# RTI-Dome-wire.net
KiCad netlist of a schematic drawn in EAGLE
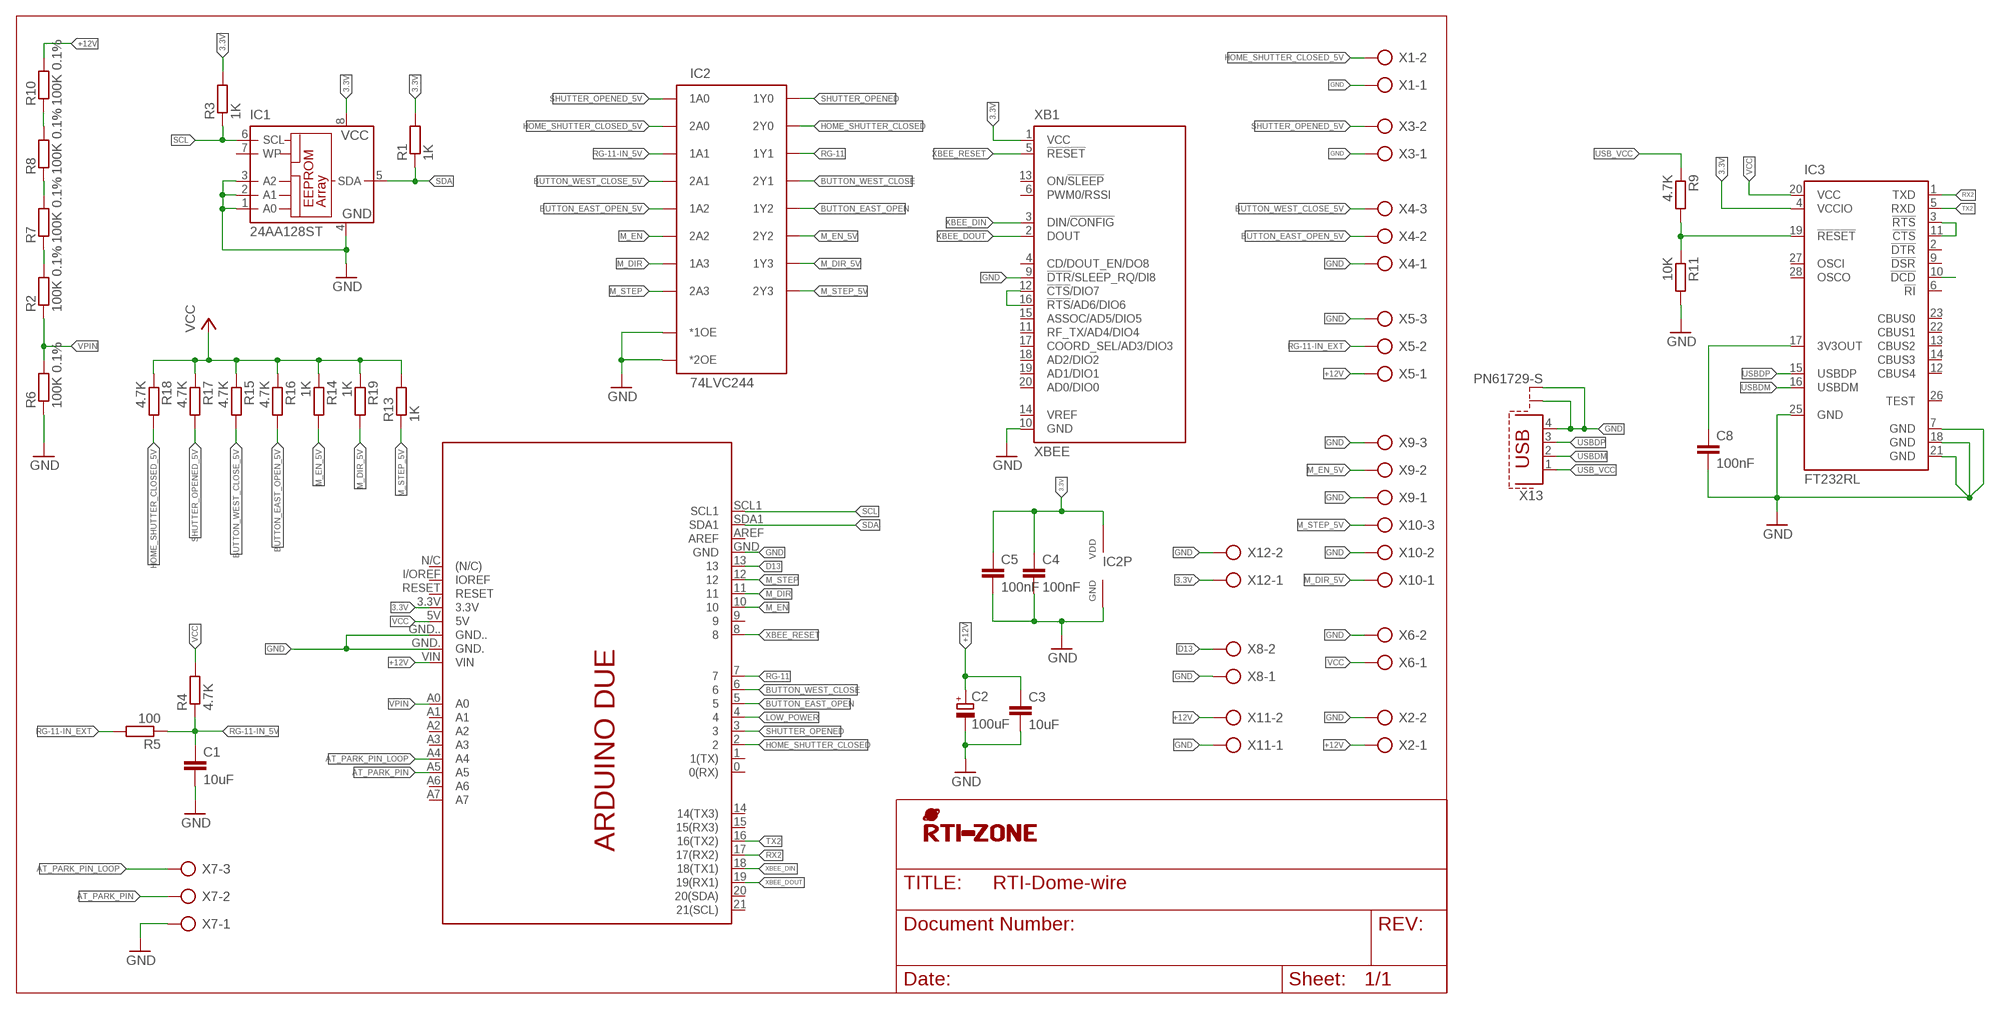
[diagram p0: schematic, sheet 1]

(export (version "E")
  (design (tool "Eeschema 10.0.6"))
  (components
    (comp (ref "C1")
      (value "10uF")
      (footprint "eagle-import:C0805")
      (libsource (lib "eagle-import") (part "C-EU'0805'"))
    )
    (comp (ref "C2")
      (value "100uF")
      (footprint "eagle-import:UD-10X10_NICHICON")
      (libsource (lib "eagle-import") (part "CPOL-EU"))
    )
    (comp (ref "C3")
      (value "10uF")
      (footprint "eagle-import:C0805")
      (libsource (lib "eagle-import") (part "C-EU'0805'"))
    )
    (comp (ref "C4")
      (value "100nF")
      (footprint "eagle-import:C0805")
      (libsource (lib "eagle-import") (part "C-EU'0805'"))
    )
    (comp (ref "C5")
      (value "100nF")
      (footprint "eagle-import:C0805")
      (libsource (lib "eagle-import") (part "C-EU'0805'"))
    )
    (comp (ref "C8")
      (value "100nF")
      (footprint "eagle-import:C0805")
      (libsource (lib "eagle-import") (part "C-EU'0805'"))
    )
    (comp (ref "IC1")
      (value "24AA128ST")
      (footprint "eagle-import:TSSOP8")
      (fields (field (name "MF") "MICROCHIP") (field (name "MPN") "24AA128-I/ST"))
      (libsource (lib "eagle-import") (part "24STAA128"))
    )
    (comp (ref "IC2")
      (value "74LVC244")
      (footprint "eagle-import:TSSOP20")
      (libsource (lib "eagle-import") (part "74244LVC"))
    )
    (comp (ref "IC3")
      (value "FT232RL")
      (footprint "eagle-import:SSOP28")
      (libsource (lib "eagle-import") (part "FT232RL"))
    )
    (comp (ref "PCB1")
      (value "ARDUINO_DUE_SHIELD_SHORT")
      (footprint "eagle-import:ARDUINO_DUE_SHIELD_SHORT")
      (libsource (lib "eagle-import") (part "ARDUINO_DUE_SHIELD_SHORT"))
    )
    (comp (ref "R1")
      (value "1K")
      (footprint "eagle-import:R0805")
      (libsource (lib "eagle-import") (part "R-EU'0805'"))
    )
    (comp (ref "R2")
      (value "100K 0.1%")
      (footprint "eagle-import:R0805")
      (libsource (lib "eagle-import") (part "R-EU'0805'"))
    )
    (comp (ref "R3")
      (value "1K")
      (footprint "eagle-import:R0805")
      (libsource (lib "eagle-import") (part "R-EU'0805'"))
    )
    (comp (ref "R4")
      (value "4.7K")
      (footprint "eagle-import:R0805")
      (libsource (lib "eagle-import") (part "R-EU'0805'"))
    )
    (comp (ref "R5")
      (value "100")
      (footprint "eagle-import:R0805")
      (libsource (lib "eagle-import") (part "R-EU'0805'"))
    )
    (comp (ref "R6")
      (value "100K 0.1%")
      (footprint "eagle-import:R0805")
      (libsource (lib "eagle-import") (part "R-EU'0805'"))
    )
    (comp (ref "R7")
      (value "100K 0.1%")
      (footprint "eagle-import:R0805")
      (libsource (lib "eagle-import") (part "R-EU'0805'"))
    )
    (comp (ref "R8")
      (value "100K 0.1%")
      (footprint "eagle-import:R0805")
      (libsource (lib "eagle-import") (part "R-EU'0805'"))
    )
    (comp (ref "R9")
      (value "4.7K")
      (footprint "eagle-import:R0805")
      (libsource (lib "eagle-import") (part "R-EU'0805'"))
    )
    (comp (ref "R10")
      (value "100K 0.1%")
      (footprint "eagle-import:R0805")
      (libsource (lib "eagle-import") (part "R-EU'0805'"))
    )
    (comp (ref "R11")
      (value "10K")
      (footprint "eagle-import:R0805")
      (libsource (lib "eagle-import") (part "R-EU'0805'"))
    )
    (comp (ref "R13")
      (value "1K")
      (footprint "eagle-import:R0805")
      (libsource (lib "eagle-import") (part "R-EU'0805'"))
    )
    (comp (ref "R14")
      (value "1K")
      (footprint "eagle-import:R0805")
      (libsource (lib "eagle-import") (part "R-EU'0805'"))
    )
    (comp (ref "R15")
      (value "4.7K")
      (footprint "eagle-import:R0805")
      (libsource (lib "eagle-import") (part "R-EU'0805'"))
    )
    (comp (ref "R16")
      (value "4.7K")
      (footprint "eagle-import:R0805")
      (libsource (lib "eagle-import") (part "R-EU'0805'"))
    )
    (comp (ref "R17")
      (value "4.7K")
      (footprint "eagle-import:R0805")
      (libsource (lib "eagle-import") (part "R-EU'0805'"))
    )
    (comp (ref "R18")
      (value "4.7K")
      (footprint "eagle-import:R0805")
      (libsource (lib "eagle-import") (part "R-EU'0805'"))
    )
    (comp (ref "R19")
      (value "1K")
      (footprint "eagle-import:R0805")
      (libsource (lib "eagle-import") (part "R-EU'0805'"))
    )
    (comp (ref "U$4")
      (value "RTI-LOGO_BIG")
      (footprint "eagle-import:LOGO_BIG")
      (libsource (lib "eagle-import") (part "RTI-LOGO_BIG"))
    )
    (comp (ref "X1")
      (value "AK500/2")
      (footprint "eagle-import:AK500_2")
      (libsource (lib "eagle-import") (part "AK500/2"))
    )
    (comp (ref "X2")
      (value "AK500/2")
      (footprint "eagle-import:AK500_2")
      (libsource (lib "eagle-import") (part "AK500/2"))
    )
    (comp (ref "X3")
      (value "AK500/2")
      (footprint "eagle-import:AK500_2")
      (libsource (lib "eagle-import") (part "AK500/2"))
    )
    (comp (ref "X4")
      (value "AK500/3")
      (footprint "eagle-import:AK500_3")
      (libsource (lib "eagle-import") (part "AK500/3"))
    )
    (comp (ref "X5")
      (value "AK500/3")
      (footprint "eagle-import:AK500_3")
      (libsource (lib "eagle-import") (part "AK500/3"))
    )
    (comp (ref "X6")
      (value "AK500/2")
      (footprint "eagle-import:AK500_2")
      (libsource (lib "eagle-import") (part "AK500/2"))
    )
    (comp (ref "X7")
      (value "AK500/3")
      (footprint "eagle-import:AK500_3")
      (libsource (lib "eagle-import") (part "AK500/3"))
    )
    (comp (ref "X8")
      (value "AK500/2")
      (footprint "eagle-import:AK500_2")
      (libsource (lib "eagle-import") (part "AK500/2"))
    )
    (comp (ref "X9")
      (value "AK500/3")
      (footprint "eagle-import:AK500_3")
      (libsource (lib "eagle-import") (part "AK500/3"))
    )
    (comp (ref "X10")
      (value "AK500/3")
      (footprint "eagle-import:AK500_3")
      (libsource (lib "eagle-import") (part "AK500/3"))
    )
    (comp (ref "X11")
      (value "AK500/2")
      (footprint "eagle-import:AK500_2")
      (libsource (lib "eagle-import") (part "AK500/2"))
    )
    (comp (ref "X12")
      (value "AK500/2")
      (footprint "eagle-import:AK500_2")
      (libsource (lib "eagle-import") (part "AK500/2"))
    )
    (comp (ref "X13")
      (value "PN61729-S")
      (footprint "eagle-import:PN61729-S")
      (libsource (lib "eagle-import") (part "PN61729-S"))
    )
    (comp (ref "XB1")
      (value "XBEE")
      (footprint "eagle-import:XBEE")
      (fields (field (name "MPN") "XBP24-Z7UIT-004"))
      (libsource (lib "eagle-import") (part "XBEE"))
    )
  )
  (nets
    (net (code "1") (name "+12V") (class "Default")
      (node (ref "C2") (pin "+") (pinfunction "+_+") (pintype "passive"))
      (node (ref "C3") (pin "1") (pinfunction "1_1") (pintype "passive"))
      (node (ref "PCB1") (pin "VIN") (pinfunction "VIN_VIN") (pintype "bidirectional"))
      (node (ref "R10") (pin "2") (pinfunction "2_2") (pintype "passive"))
      (node (ref "X11") (pin "2") (pinfunction "KL_2") (pintype "passive"))
      (node (ref "X2") (pin "1") (pinfunction "KL_1") (pintype "passive"))
      (node (ref "X5") (pin "1") (pinfunction "KL_1") (pintype "passive"))
    )
    (net (code "2") (name "3.3V") (class "Default")
      (node (ref "C4") (pin "1") (pinfunction "1_1") (pintype "passive"))
      (node (ref "C5") (pin "1") (pinfunction "1_1") (pintype "passive"))
      (node (ref "IC1") (pin "8") (pinfunction "VCC_8") (pintype "power_in"))
      (node (ref "IC2") (pin "P$20") (pinfunction "VDD_P$20") (pintype "power_in"))
      (node (ref "IC3") (pin "4") (pinfunction "VCCIO_4") (pintype "power_in"))
      (node (ref "PCB1") (pin "3.3V") (pinfunction "3.3V_3.3V") (pintype "bidirectional"))
      (node (ref "R1") (pin "2") (pinfunction "2_2") (pintype "passive"))
      (node (ref "R3") (pin "2") (pinfunction "2_2") (pintype "passive"))
      (node (ref "X12") (pin "1") (pinfunction "KL_1") (pintype "passive"))
      (node (ref "XB1") (pin "1") (pinfunction "VCC_1") (pintype "power_in"))
    )
    (net (code "3") (name "AT_PARK_PIN") (class "Default")
      (node (ref "PCB1") (pin "A5") (pinfunction "A5_A5") (pintype "bidirectional"))
      (node (ref "X7") (pin "2") (pinfunction "KL_2") (pintype "passive"))
    )
    (net (code "4") (name "AT_PARK_PIN_LOOP") (class "Default")
      (node (ref "PCB1") (pin "A4") (pinfunction "A4_A4") (pintype "bidirectional"))
      (node (ref "X7") (pin "3") (pinfunction "KL_3") (pintype "passive"))
    )
    (net (code "5") (name "BUTTON_EAST_OPEN") (class "Default")
      (node (ref "IC2") (pin "P$14") (pinfunction "1Y2_P$14") (pintype "output"))
      (node (ref "PCB1") (pin "5") (pinfunction "5_5") (pintype "bidirectional"))
    )
    (net (code "6") (name "BUTTON_EAST_OPEN_5V") (class "Default")
      (node (ref "IC2") (pin "P$6") (pinfunction "1A2_P$6") (pintype "input"))
      (node (ref "R16") (pin "2") (pinfunction "2_2") (pintype "passive"))
      (node (ref "X4") (pin "2") (pinfunction "KL_2") (pintype "passive"))
    )
    (net (code "7") (name "BUTTON_WEST_CLOSE") (class "Default")
      (node (ref "IC2") (pin "P$5") (pinfunction "2Y1_P$5") (pintype "output"))
      (node (ref "PCB1") (pin "6") (pinfunction "6_6") (pintype "bidirectional"))
    )
    (net (code "8") (name "BUTTON_WEST_CLOSE_5V") (class "Default")
      (node (ref "IC2") (pin "P$15") (pinfunction "2A1_P$15") (pintype "input"))
      (node (ref "R15") (pin "2") (pinfunction "2_2") (pintype "passive"))
      (node (ref "X4") (pin "3") (pinfunction "KL_3") (pintype "passive"))
    )
    (net (code "9") (name "D13") (class "Default")
      (node (ref "PCB1") (pin "13") (pinfunction "13_13") (pintype "bidirectional"))
      (node (ref "X8") (pin "2") (pinfunction "KL_2") (pintype "passive"))
    )
    (net (code "10") (name "GND") (class "Default")
      (node (ref "C1") (pin "2") (pinfunction "2_2") (pintype "passive"))
      (node (ref "C2") (pin "-") (pinfunction "-_-") (pintype "passive"))
      (node (ref "C3") (pin "2") (pinfunction "2_2") (pintype "passive"))
      (node (ref "C4") (pin "2") (pinfunction "2_2") (pintype "passive"))
      (node (ref "C5") (pin "2") (pinfunction "2_2") (pintype "passive"))
      (node (ref "C8") (pin "2") (pinfunction "2_2") (pintype "passive"))
      (node (ref "IC1") (pin "1") (pinfunction "A0_1") (pintype "input"))
      (node (ref "IC1") (pin "2") (pinfunction "A1_2") (pintype "input"))
      (node (ref "IC1") (pin "3") (pinfunction "A2_3") (pintype "input"))
      (node (ref "IC1") (pin "4") (pinfunction "GND_4") (pintype "power_in"))
      (node (ref "IC2") (pin "P$1") (pinfunction "*1OE_P$1") (pintype "input"))
      (node (ref "IC2") (pin "P$10") (pinfunction "GND_P$10") (pintype "power_in"))
      (node (ref "IC2") (pin "P$19") (pinfunction "*2OE_P$19") (pintype "input"))
      (node (ref "IC3") (pin "18") (pinfunction "GND_18") (pintype "power_in"))
      (node (ref "IC3") (pin "21") (pinfunction "GND_21") (pintype "power_in"))
      (node (ref "IC3") (pin "25") (pinfunction "GND_25") (pintype "power_in"))
      (node (ref "IC3") (pin "7") (pinfunction "GND_7") (pintype "power_in"))
      (node (ref "PCB1") (pin "GND") (pinfunction "GND_GND") (pintype "bidirectional"))
      (node (ref "PCB1") (pin "GND.") (pinfunction "GND._GND.") (pintype "bidirectional"))
      (node (ref "PCB1") (pin "GND..") (pinfunction "GND.._GND..") (pintype "bidirectional"))
      (node (ref "R11") (pin "2") (pinfunction "2_2") (pintype "passive"))
      (node (ref "R6") (pin "1") (pinfunction "1_1") (pintype "passive"))
      (node (ref "X1") (pin "1") (pinfunction "KL_1") (pintype "passive"))
      (node (ref "X10") (pin "2") (pinfunction "KL_2") (pintype "passive"))
      (node (ref "X11") (pin "1") (pinfunction "KL_1") (pintype "passive"))
      (node (ref "X12") (pin "2") (pinfunction "KL_2") (pintype "passive"))
      (node (ref "X13") (pin "4") (pinfunction "4_4") (pintype "passive"))
      (node (ref "X13") (pin "S1") (pinfunction "S1_S1") (pintype "passive"))
      (node (ref "X13") (pin "S2") (pinfunction "S2_S2") (pintype "passive"))
      (node (ref "X2") (pin "2") (pinfunction "KL_2") (pintype "passive"))
      (node (ref "X3") (pin "1") (pinfunction "KL_1") (pintype "passive"))
      (node (ref "X4") (pin "1") (pinfunction "KL_1") (pintype "passive"))
      (node (ref "X5") (pin "3") (pinfunction "KL_3") (pintype "passive"))
      (node (ref "X6") (pin "2") (pinfunction "KL_2") (pintype "passive"))
      (node (ref "X7") (pin "1") (pinfunction "KL_1") (pintype "passive"))
      (node (ref "X8") (pin "1") (pinfunction "KL_1") (pintype "passive"))
      (node (ref "X9") (pin "1") (pinfunction "KL_1") (pintype "passive"))
      (node (ref "X9") (pin "3") (pinfunction "KL_3") (pintype "passive"))
      (node (ref "XB1") (pin "10") (pinfunction "GND_10") (pintype "power_in"))
      (node (ref "XB1") (pin "9") (pinfunction "~{DTR}/SLEEP_RQ/DI8_9") (pintype "bidirectional"))
    )
    (net (code "11") (name "HOME_SHUTTER_CLOSED") (class "Default")
      (node (ref "IC2") (pin "P$3") (pinfunction "2Y0_P$3") (pintype "output"))
      (node (ref "PCB1") (pin "2") (pinfunction "2_2") (pintype "bidirectional"))
    )
    (net (code "12") (name "HOME_SHUTTER_CLOSED_5V") (class "Default")
      (node (ref "IC2") (pin "P$17") (pinfunction "2A0_P$17") (pintype "input"))
      (node (ref "R18") (pin "2") (pinfunction "2_2") (pintype "passive"))
      (node (ref "X1") (pin "2") (pinfunction "KL_2") (pintype "passive"))
    )
    (net (code "13") (name "LOW_POWER") (class "Default")
      (node (ref "PCB1") (pin "4") (pinfunction "4_4") (pintype "bidirectional"))
    )
    (net (code "14") (name "M_DIR") (class "Default")
      (node (ref "IC2") (pin "P$8") (pinfunction "1A3_P$8") (pintype "input"))
      (node (ref "PCB1") (pin "11") (pinfunction "11_11") (pintype "bidirectional"))
    )
    (net (code "15") (name "M_DIR_5V") (class "Default")
      (node (ref "IC2") (pin "P$12") (pinfunction "1Y3_P$12") (pintype "output"))
      (node (ref "R19") (pin "2") (pinfunction "2_2") (pintype "passive"))
      (node (ref "X10") (pin "1") (pinfunction "KL_1") (pintype "passive"))
    )
    (net (code "16") (name "M_EN") (class "Default")
      (node (ref "IC2") (pin "P$13") (pinfunction "2A2_P$13") (pintype "input"))
      (node (ref "PCB1") (pin "10") (pinfunction "10_10") (pintype "bidirectional"))
    )
    (net (code "17") (name "M_EN_5V") (class "Default")
      (node (ref "IC2") (pin "P$7") (pinfunction "2Y2_P$7") (pintype "output"))
      (node (ref "R14") (pin "2") (pinfunction "2_2") (pintype "passive"))
      (node (ref "X9") (pin "2") (pinfunction "KL_2") (pintype "passive"))
    )
    (net (code "18") (name "M_STEP") (class "Default")
      (node (ref "IC2") (pin "P$11") (pinfunction "2A3_P$11") (pintype "input"))
      (node (ref "PCB1") (pin "12") (pinfunction "12_12") (pintype "bidirectional"))
    )
    (net (code "19") (name "M_STEP_5V") (class "Default")
      (node (ref "IC2") (pin "P$9") (pinfunction "2Y3_P$9") (pintype "output"))
      (node (ref "R13") (pin "1") (pinfunction "1_1") (pintype "passive"))
      (node (ref "X10") (pin "3") (pinfunction "KL_3") (pintype "passive"))
    )
    (net (code "20") (name "Net-(IC3-3V3OUT)") (class "Default")
      (node (ref "C8") (pin "1") (pinfunction "1_1") (pintype "passive"))
      (node (ref "IC3") (pin "17") (pinfunction "3V3OUT_17") (pintype "output"))
    )
    (net (code "21") (name "Net-(IC3-~{CTS})") (class "Default")
      (node (ref "IC3") (pin "11") (pinfunction "~{CTS}_11") (pintype "input"))
      (node (ref "IC3") (pin "3") (pinfunction "~{RTS}_3") (pintype "output"))
    )
    (net (code "22") (name "Net-(IC3-~{RESET})") (class "Default")
      (node (ref "IC3") (pin "19") (pinfunction "~{RESET}_19") (pintype "input"))
      (node (ref "R11") (pin "1") (pinfunction "1_1") (pintype "passive"))
      (node (ref "R9") (pin "2") (pinfunction "2_2") (pintype "passive"))
    )
    (net (code "23") (name "Net-(R2-Pad2)") (class "Default")
      (node (ref "R2") (pin "2") (pinfunction "2_2") (pintype "passive"))
      (node (ref "R7") (pin "1") (pinfunction "1_1") (pintype "passive"))
    )
    (net (code "24") (name "Net-(R7-Pad2)") (class "Default")
      (node (ref "R7") (pin "2") (pinfunction "2_2") (pintype "passive"))
      (node (ref "R8") (pin "1") (pinfunction "1_1") (pintype "passive"))
    )
    (net (code "25") (name "Net-(R10-Pad1)") (class "Default")
      (node (ref "R10") (pin "1") (pinfunction "1_1") (pintype "passive"))
      (node (ref "R8") (pin "2") (pinfunction "2_2") (pintype "passive"))
    )
    (net (code "26") (name "Net-(XB1-~{CTS}{slash}DIO7)") (class "Default")
      (node (ref "XB1") (pin "12") (pinfunction "~{CTS}/DIO7_12") (pintype "bidirectional"))
      (node (ref "XB1") (pin "16") (pinfunction "~{RTS}/AD6/DIO6_16") (pintype "bidirectional"))
    )
    (net (code "27") (name "RG-11") (class "Default")
      (node (ref "IC2") (pin "P$16") (pinfunction "1Y1_P$16") (pintype "output"))
      (node (ref "PCB1") (pin "7") (pinfunction "7_7") (pintype "bidirectional"))
    )
    (net (code "28") (name "RG-11-IN_5V") (class "Default")
      (node (ref "C1") (pin "1") (pinfunction "1_1") (pintype "passive"))
      (node (ref "IC2") (pin "P$4") (pinfunction "1A1_P$4") (pintype "input"))
      (node (ref "R4") (pin "1") (pinfunction "1_1") (pintype "passive"))
      (node (ref "R5") (pin "1") (pinfunction "1_1") (pintype "passive"))
    )
    (net (code "29") (name "RG-11-IN_EXT") (class "Default")
      (node (ref "R5") (pin "2") (pinfunction "2_2") (pintype "passive"))
      (node (ref "X5") (pin "2") (pinfunction "KL_2") (pintype "passive"))
    )
    (net (code "30") (name "RX2") (class "Default")
      (node (ref "IC3") (pin "1") (pinfunction "TXD_1") (pintype "output"))
      (node (ref "PCB1") (pin "17") (pinfunction "17(RX2)_17") (pintype "bidirectional"))
    )
    (net (code "31") (name "SCL") (class "Default")
      (node (ref "IC1") (pin "6") (pinfunction "SCL_6") (pintype "input"))
      (node (ref "PCB1") (pin "SCL1") (pinfunction "SCL1_SCL1") (pintype "bidirectional"))
      (node (ref "R3") (pin "1") (pinfunction "1_1") (pintype "passive"))
    )
    (net (code "32") (name "SDA") (class "Default")
      (node (ref "IC1") (pin "5") (pinfunction "SDA_5") (pintype "bidirectional"))
      (node (ref "PCB1") (pin "SDA1") (pinfunction "SDA1_SDA1") (pintype "bidirectional"))
      (node (ref "R1") (pin "1") (pinfunction "1_1") (pintype "passive"))
    )
    (net (code "33") (name "SHUTTER_OPENED") (class "Default")
      (node (ref "IC2") (pin "P$18") (pinfunction "1Y0_P$18") (pintype "output"))
      (node (ref "PCB1") (pin "3") (pinfunction "3_3") (pintype "bidirectional"))
    )
    (net (code "34") (name "SHUTTER_OPENED_5V") (class "Default")
      (node (ref "IC2") (pin "P$2") (pinfunction "1A0_P$2") (pintype "input"))
      (node (ref "R17") (pin "2") (pinfunction "2_2") (pintype "passive"))
      (node (ref "X3") (pin "2") (pinfunction "KL_2") (pintype "passive"))
    )
    (net (code "35") (name "TX2") (class "Default")
      (node (ref "IC3") (pin "5") (pinfunction "RXD_5") (pintype "input"))
      (node (ref "PCB1") (pin "16") (pinfunction "16(TX2)_16") (pintype "bidirectional"))
    )
    (net (code "36") (name "USBDM") (class "Default")
      (node (ref "IC3") (pin "16") (pinfunction "USBDM_16") (pintype "bidirectional"))
      (node (ref "X13") (pin "2") (pinfunction "2_2") (pintype "passive"))
    )
    (net (code "37") (name "USBDP") (class "Default")
      (node (ref "IC3") (pin "15") (pinfunction "USBDP_15") (pintype "bidirectional"))
      (node (ref "X13") (pin "3") (pinfunction "3_3") (pintype "passive"))
    )
    (net (code "38") (name "USB_VCC") (class "Default")
      (node (ref "R9") (pin "1") (pinfunction "1_1") (pintype "passive"))
      (node (ref "X13") (pin "1") (pinfunction "1_1") (pintype "passive"))
    )
    (net (code "39") (name "VCC") (class "Default")
      (node (ref "IC3") (pin "20") (pinfunction "VCC_20") (pintype "power_in"))
      (node (ref "PCB1") (pin "5V") (pinfunction "5V_5V") (pintype "bidirectional"))
      (node (ref "R13") (pin "2") (pinfunction "2_2") (pintype "passive"))
      (node (ref "R14") (pin "1") (pinfunction "1_1") (pintype "passive"))
      (node (ref "R15") (pin "1") (pinfunction "1_1") (pintype "passive"))
      (node (ref "R16") (pin "1") (pinfunction "1_1") (pintype "passive"))
      (node (ref "R17") (pin "1") (pinfunction "1_1") (pintype "passive"))
      (node (ref "R18") (pin "1") (pinfunction "1_1") (pintype "passive"))
      (node (ref "R19") (pin "1") (pinfunction "1_1") (pintype "passive"))
      (node (ref "R4") (pin "2") (pinfunction "2_2") (pintype "passive"))
      (node (ref "X6") (pin "1") (pinfunction "KL_1") (pintype "passive"))
    )
    (net (code "40") (name "VPIN") (class "Default")
      (node (ref "PCB1") (pin "A0") (pinfunction "A0_A0") (pintype "bidirectional"))
      (node (ref "R2") (pin "1") (pinfunction "1_1") (pintype "passive"))
      (node (ref "R6") (pin "2") (pinfunction "2_2") (pintype "passive"))
    )
    (net (code "41") (name "XBEE_DIN") (class "Default")
      (node (ref "PCB1") (pin "18") (pinfunction "18(TX1)_18") (pintype "bidirectional"))
      (node (ref "XB1") (pin "3") (pinfunction "DIN/~{CONFIG}_3") (pintype "input"))
    )
    (net (code "42") (name "XBEE_DOUT") (class "Default")
      (node (ref "PCB1") (pin "19") (pinfunction "19(RX1)_19") (pintype "bidirectional"))
      (node (ref "XB1") (pin "2") (pinfunction "DOUT_2") (pintype "output"))
    )
    (net (code "43") (name "XBEE_RESET") (class "Default")
      (node (ref "PCB1") (pin "8") (pinfunction "8_8") (pintype "bidirectional"))
      (node (ref "XB1") (pin "5") (pinfunction "~{RESET}_5") (pintype "input"))
    )
    (net (code "44") (name "unconnected-(IC1-WP-Pad7)") (class "Default")
      (node (ref "IC1") (pin "7") (pinfunction "WP_7") (pintype "input"))
    )
    (net (code "45") (name "unconnected-(IC3-CBUS0-Pad23)") (class "Default")
      (node (ref "IC3") (pin "23") (pinfunction "CBUS0_23") (pintype "bidirectional"))
    )
    (net (code "46") (name "unconnected-(IC3-CBUS1-Pad22)") (class "Default")
      (node (ref "IC3") (pin "22") (pinfunction "CBUS1_22") (pintype "bidirectional"))
    )
    (net (code "47") (name "unconnected-(IC3-CBUS2-Pad13)") (class "Default")
      (node (ref "IC3") (pin "13") (pinfunction "CBUS2_13") (pintype "bidirectional"))
    )
    (net (code "48") (name "unconnected-(IC3-CBUS3-Pad14)") (class "Default")
      (node (ref "IC3") (pin "14") (pinfunction "CBUS3_14") (pintype "bidirectional"))
    )
    (net (code "49") (name "unconnected-(IC3-CBUS4-Pad12)") (class "Default")
      (node (ref "IC3") (pin "12") (pinfunction "CBUS4_12") (pintype "bidirectional"))
    )
    (net (code "50") (name "unconnected-(IC3-OSCI-Pad27)") (class "Default")
      (node (ref "IC3") (pin "27") (pinfunction "OSCI_27") (pintype "input"))
    )
    (net (code "51") (name "unconnected-(IC3-OSCO-Pad28)") (class "Default")
      (node (ref "IC3") (pin "28") (pinfunction "OSCO_28") (pintype "output"))
    )
    (net (code "52") (name "unconnected-(IC3-TEST-Pad26)") (class "Default")
      (node (ref "IC3") (pin "26") (pinfunction "TEST_26") (pintype "input"))
    )
    (net (code "53") (name "unconnected-(IC3-~{DCD}-Pad10)") (class "Default")
      (node (ref "IC3") (pin "10") (pinfunction "~{DCD}_10") (pintype "input"))
    )
    (net (code "54") (name "unconnected-(IC3-~{DSR}-Pad9)") (class "Default")
      (node (ref "IC3") (pin "9") (pinfunction "~{DSR}_9") (pintype "input"))
    )
    (net (code "55") (name "unconnected-(IC3-~{DTR}-Pad2)") (class "Default")
      (node (ref "IC3") (pin "2") (pinfunction "~{DTR}_2") (pintype "output"))
    )
    (net (code "56") (name "unconnected-(IC3-~{RI}-Pad6)") (class "Default")
      (node (ref "IC3") (pin "6") (pinfunction "~{RI}_6") (pintype "input"))
    )
    (net (code "57") (name "unconnected-(PCB1-(N{slash}C)-PadN{slash}C)") (class "Default")
      (node (ref "PCB1") (pin "N/C") (pinfunction "(N/C)_N/C") (pintype "bidirectional"))
    )
    (net (code "58") (name "unconnected-(PCB1-0(RX)-Pad0)") (class "Default")
      (node (ref "PCB1") (pin "0") (pinfunction "0(RX)_0") (pintype "bidirectional"))
    )
    (net (code "59") (name "unconnected-(PCB1-1(TX)-Pad1)") (class "Default")
      (node (ref "PCB1") (pin "1") (pinfunction "1(TX)_1") (pintype "bidirectional"))
    )
    (net (code "60") (name "unconnected-(PCB1-14(TX3)-Pad14)") (class "Default")
      (node (ref "PCB1") (pin "14") (pinfunction "14(TX3)_14") (pintype "bidirectional"))
    )
    (net (code "61") (name "unconnected-(PCB1-15(RX3)-Pad15)") (class "Default")
      (node (ref "PCB1") (pin "15") (pinfunction "15(RX3)_15") (pintype "bidirectional"))
    )
    (net (code "62") (name "unconnected-(PCB1-20(SDA)-Pad20)") (class "Default")
      (node (ref "PCB1") (pin "20") (pinfunction "20(SDA)_20") (pintype "bidirectional"))
    )
    (net (code "63") (name "unconnected-(PCB1-21(SCL)-Pad21)") (class "Default")
      (node (ref "PCB1") (pin "21") (pinfunction "21(SCL)_21") (pintype "bidirectional"))
    )
    (net (code "64") (name "unconnected-(PCB1-IOREF-PadI{slash}OREF)") (class "Default")
      (node (ref "PCB1") (pin "I/OREF") (pinfunction "IOREF_I/OREF") (pintype "bidirectional"))
    )
    (net (code "65") (name "unconnected-(PCB1-Pad9)") (class "Default")
      (node (ref "PCB1") (pin "9") (pinfunction "9_9") (pintype "bidirectional"))
    )
    (net (code "66") (name "unconnected-(PCB1-PadA1)") (class "Default")
      (node (ref "PCB1") (pin "A1") (pinfunction "A1_A1") (pintype "bidirectional"))
    )
    (net (code "67") (name "unconnected-(PCB1-PadA2)") (class "Default")
      (node (ref "PCB1") (pin "A2") (pinfunction "A2_A2") (pintype "bidirectional"))
    )
    (net (code "68") (name "unconnected-(PCB1-PadA3)") (class "Default")
      (node (ref "PCB1") (pin "A3") (pinfunction "A3_A3") (pintype "bidirectional"))
    )
    (net (code "69") (name "unconnected-(PCB1-PadA6)") (class "Default")
      (node (ref "PCB1") (pin "A6") (pinfunction "A6_A6") (pintype "bidirectional"))
    )
    (net (code "70") (name "unconnected-(PCB1-PadA7)") (class "Default")
      (node (ref "PCB1") (pin "A7") (pinfunction "A7_A7") (pintype "bidirectional"))
    )
    (net (code "71") (name "unconnected-(PCB1-PadAREF)") (class "Default")
      (node (ref "PCB1") (pin "AREF") (pinfunction "AREF_AREF") (pintype "bidirectional"))
    )
    (net (code "72") (name "unconnected-(PCB1-PadRESET)") (class "Default")
      (node (ref "PCB1") (pin "RESET") (pinfunction "RESET_RESET") (pintype "bidirectional"))
    )
    (net (code "73") (name "unconnected-(XB1-AD0{slash}DIO0-Pad20)") (class "Default")
      (node (ref "XB1") (pin "20") (pinfunction "AD0/DIO0_20") (pintype "bidirectional"))
    )
    (net (code "74") (name "unconnected-(XB1-AD1{slash}DIO1-Pad19)") (class "Default")
      (node (ref "XB1") (pin "19") (pinfunction "AD1/DIO1_19") (pintype "bidirectional"))
    )
    (net (code "75") (name "unconnected-(XB1-AD2{slash}DIO2-Pad18)") (class "Default")
      (node (ref "XB1") (pin "18") (pinfunction "AD2/DIO2_18") (pintype "bidirectional"))
    )
    (net (code "76") (name "unconnected-(XB1-ASSOC{slash}AD5{slash}DIO5-Pad15)") (class "Default")
      (node (ref "XB1") (pin "15") (pinfunction "ASSOC/AD5/DIO5_15") (pintype "bidirectional"))
    )
    (net (code "77") (name "unconnected-(XB1-CD{slash}DOUT_EN{slash}DO8-Pad4)") (class "Default")
      (node (ref "XB1") (pin "4") (pinfunction "CD/DOUT_EN/DO8_4") (pintype "output"))
    )
    (net (code "78") (name "unconnected-(XB1-COORD_SEL{slash}AD3{slash}DIO3-Pad17)") (class "Default")
      (node (ref "XB1") (pin "17") (pinfunction "COORD_SEL/AD3/DIO3_17") (pintype "bidirectional"))
    )
    (net (code "79") (name "unconnected-(XB1-ON{slash}~{SLEEP}-Pad13)") (class "Default")
      (node (ref "XB1") (pin "13") (pinfunction "ON/~{SLEEP}_13") (pintype "output"))
    )
    (net (code "80") (name "unconnected-(XB1-PWM0{slash}RSSI-Pad6)") (class "Default")
      (node (ref "XB1") (pin "6") (pinfunction "PWM0/RSSI_6") (pintype "output"))
    )
    (net (code "81") (name "unconnected-(XB1-RF_TX{slash}AD4{slash}DIO4-Pad11)") (class "Default")
      (node (ref "XB1") (pin "11") (pinfunction "RF_TX/AD4/DIO4_11") (pintype "bidirectional"))
    )
    (net (code "82") (name "unconnected-(XB1-VREF-Pad14)") (class "Default")
      (node (ref "XB1") (pin "14") (pinfunction "VREF_14") (pintype "input"))
    )
  )
)
